# minimote.net
KiCad netlist of a schematic drawn in EAGLE
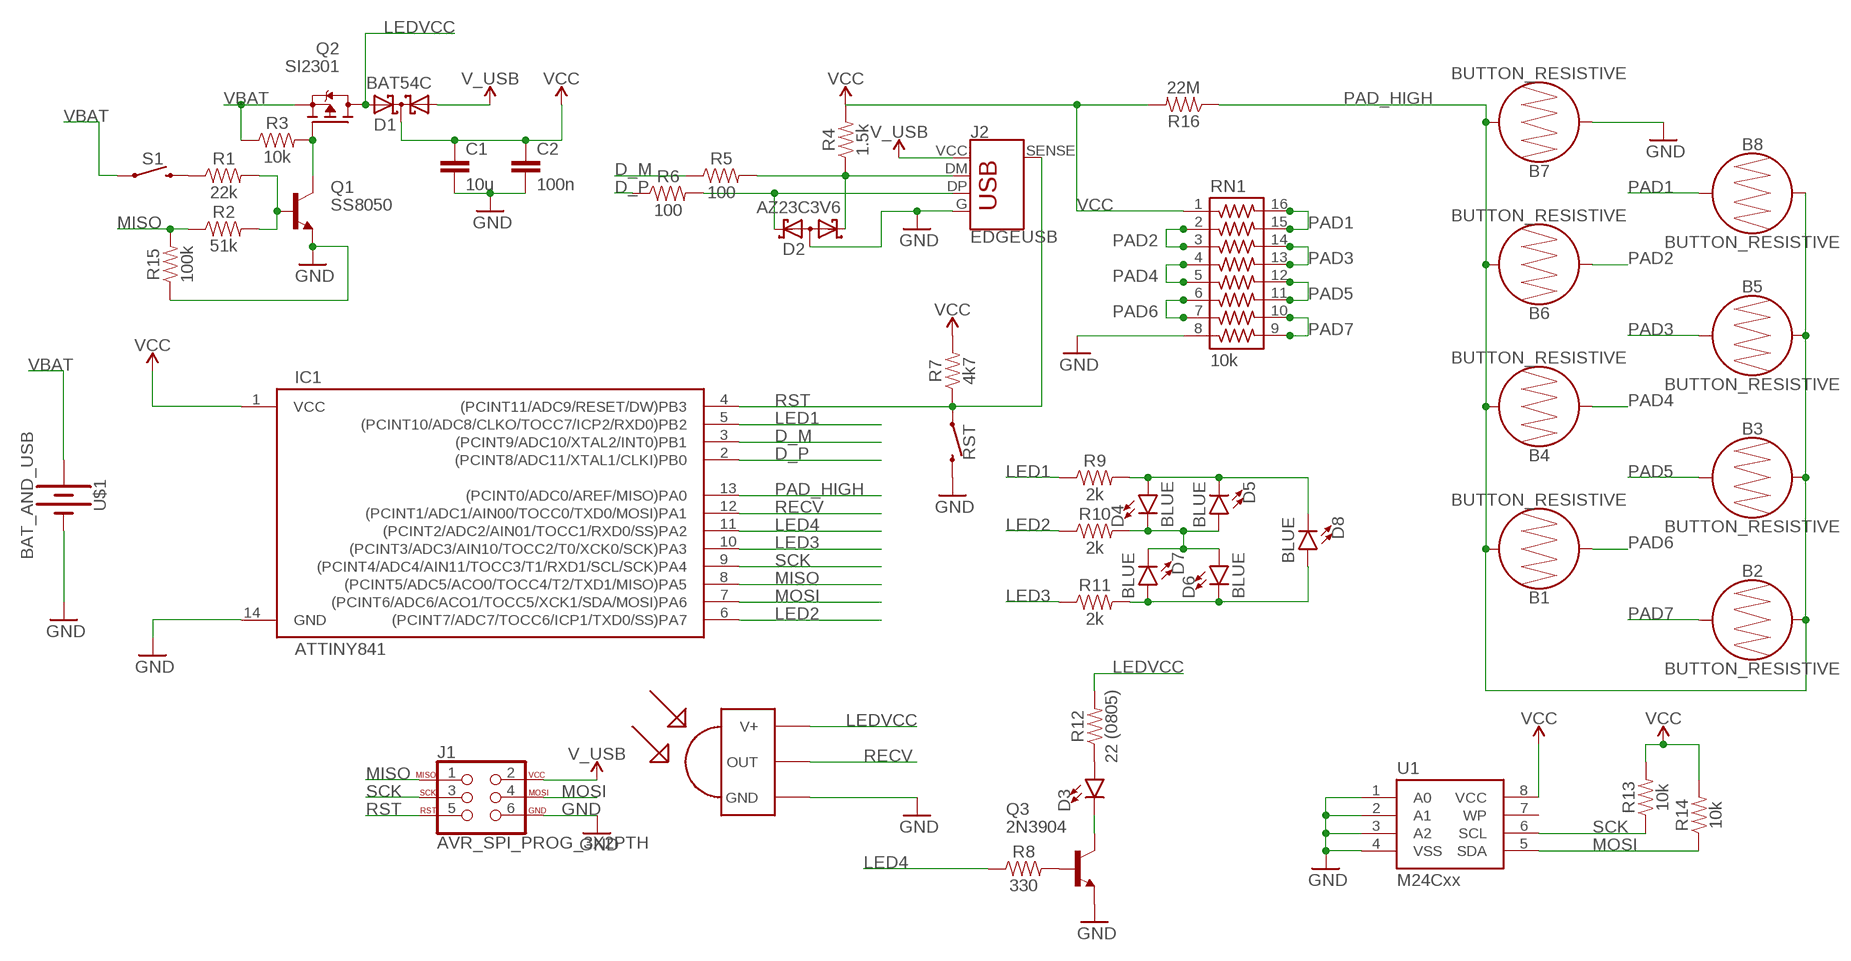
[diagram p0: schematic, sheet 1]

(export (version "E")
  (design (tool "Eeschema 10.0.6"))
  (components
    (comp (ref "B1")
      (value "BUTTON_RESISTIVE")
      (footprint "eagle-import:BUTTON-CONDUCTIVE")
      (libsource (lib "eagle-import") (part "BUTTON_RESISTIVE"))
    )
    (comp (ref "B2")
      (value "BUTTON_RESISTIVE")
      (footprint "eagle-import:BUTTON-CONDUCTIVE")
      (libsource (lib "eagle-import") (part "BUTTON_RESISTIVE"))
    )
    (comp (ref "B3")
      (value "BUTTON_RESISTIVE")
      (footprint "eagle-import:BUTTON-CONDUCTIVE")
      (libsource (lib "eagle-import") (part "BUTTON_RESISTIVE"))
    )
    (comp (ref "B4")
      (value "BUTTON_RESISTIVE")
      (footprint "eagle-import:BUTTON-CONDUCTIVE")
      (libsource (lib "eagle-import") (part "BUTTON_RESISTIVE"))
    )
    (comp (ref "B5")
      (value "BUTTON_RESISTIVE")
      (footprint "eagle-import:BUTTON-CONDUCTIVE")
      (libsource (lib "eagle-import") (part "BUTTON_RESISTIVE"))
    )
    (comp (ref "B6")
      (value "BUTTON_RESISTIVE")
      (footprint "eagle-import:BUTTON-CONDUCTIVE")
      (libsource (lib "eagle-import") (part "BUTTON_RESISTIVE"))
    )
    (comp (ref "B7")
      (value "BUTTON_RESISTIVE")
      (footprint "eagle-import:BUTTON-CONDUCTIVE")
      (libsource (lib "eagle-import") (part "BUTTON_RESISTIVE"))
    )
    (comp (ref "B8")
      (value "BUTTON_RESISTIVE")
      (footprint "eagle-import:BUTTON-CONDUCTIVE")
      (libsource (lib "eagle-import") (part "BUTTON_RESISTIVE"))
    )
    (comp (ref "C1")
      (value "10u")
      (footprint "eagle-import:0603")
      (libsource (lib "eagle-import") (part "10UF-0603-6.3V-20%"))
    )
    (comp (ref "C2")
      (value "100n")
      (footprint "eagle-import:0603")
      (libsource (lib "eagle-import") (part "10UF-0603-6.3V-20%"))
    )
    (comp (ref "D1")
      (value "BAT54C")
      (footprint "eagle-import:SOT23")
      (libsource (lib "eagle-import") (part "BAT54C"))
    )
    (comp (ref "D2")
      (value "AZ23C3V6")
      (footprint "eagle-import:SOT23")
      (libsource (lib "eagle-import") (part "AZ23C3V6"))
    )
    (comp (ref "D3")
      (value "LED3MM")
      (footprint "eagle-import:LED_3MM")
      (libsource (lib "eagle-import") (part "LED3MM"))
    )
    (comp (ref "D4")
      (value "BLUE")
      (footprint "eagle-import:LED-0603")
      (libsource (lib "eagle-import") (part "LED-BLUE0603"))
    )
    (comp (ref "D5")
      (value "BLUE")
      (footprint "eagle-import:LED-0603")
      (libsource (lib "eagle-import") (part "LED-BLUE0603"))
    )
    (comp (ref "D6")
      (value "BLUE")
      (footprint "eagle-import:LED-0603")
      (libsource (lib "eagle-import") (part "LED-BLUE0603"))
    )
    (comp (ref "D7")
      (value "BLUE")
      (footprint "eagle-import:LED-0603")
      (libsource (lib "eagle-import") (part "LED-BLUE0603"))
    )
    (comp (ref "D8")
      (value "BLUE")
      (footprint "eagle-import:LED-0603")
      (libsource (lib "eagle-import") (part "LED-BLUE0603"))
    )
    (comp (ref "IC1")
      (value "ATTINY841")
      (footprint "eagle-import:SOIC14N")
      (libsource (lib "eagle-import") (part "ATTINY441/841-SSU"))
    )
    (comp (ref "J1")
      (value "AVR_SPI_PROG_3X2PTH")
      (footprint "eagle-import:2X3")
      (libsource (lib "eagle-import") (part "AVR_SPI_PROG_3X2PTH"))
    )
    (comp (ref "J2")
      (value "EDGEUSB")
      (footprint "eagle-import:USBPCB")
      (libsource (lib "eagle-import") (part "EDGEUSB"))
    )
    (comp (ref "Q1")
      (value "SS8050")
      (footprint "eagle-import:SOT23")
      (libsource (lib "eagle-import") (part "SS8050"))
    )
    (comp (ref "Q2")
      (value "SI2301")
      (footprint "eagle-import:SOT23")
      (libsource (lib "eagle-import") (part "SI2301"))
    )
    (comp (ref "Q3")
      (value "2N3904")
      (footprint "eagle-import:SOT23-BEC")
      (libsource (lib "eagle-import") (part "-NPN-SOT23-BECMMBT3904LT1"))
    )
    (comp (ref "R1")
      (value "22k")
      (footprint "eagle-import:0603")
      (libsource (lib "eagle-import") (part "3.3KOHM-0603-1/10W-1%"))
    )
    (comp (ref "R2")
      (value "51k")
      (footprint "eagle-import:0603")
      (libsource (lib "eagle-import") (part "3.3KOHM-0603-1/10W-1%"))
    )
    (comp (ref "R3")
      (value "10k")
      (footprint "eagle-import:0603")
      (libsource (lib "eagle-import") (part "3.3KOHM-0603-1/10W-1%"))
    )
    (comp (ref "R4")
      (value "1.5k")
      (footprint "eagle-import:0603")
      (libsource (lib "eagle-import") (part "3.3KOHM-0603-1/10W-1%"))
    )
    (comp (ref "R5")
      (value "100")
      (footprint "eagle-import:0603")
      (libsource (lib "eagle-import") (part "3.3KOHM-0603-1/10W-1%"))
    )
    (comp (ref "R6")
      (value "100")
      (footprint "eagle-import:0603")
      (libsource (lib "eagle-import") (part "3.3KOHM-0603-1/10W-1%"))
    )
    (comp (ref "R7")
      (value "4k7")
      (footprint "eagle-import:0603")
      (libsource (lib "eagle-import") (part "3.3KOHM-0603-1/10W-1%"))
    )
    (comp (ref "R8")
      (value "330")
      (footprint "eagle-import:0603")
      (libsource (lib "eagle-import") (part "3.3KOHM-0603-1/10W-1%"))
    )
    (comp (ref "R9")
      (value "2k")
      (footprint "eagle-import:0603")
      (libsource (lib "eagle-import") (part "3.3KOHM-0603-1/10W-1%"))
    )
    (comp (ref "R10")
      (value "2k")
      (footprint "eagle-import:0603")
      (libsource (lib "eagle-import") (part "3.3KOHM-0603-1/10W-1%"))
    )
    (comp (ref "R11")
      (value "2k")
      (footprint "eagle-import:0603")
      (libsource (lib "eagle-import") (part "3.3KOHM-0603-1/10W-1%"))
    )
    (comp (ref "R12")
      (value "22 (0805)")
      (footprint "eagle-import:0805")
      (libsource (lib "eagle-import") (part "0.22OHM-0805-1/4W-1%"))
    )
    (comp (ref "R13")
      (value "10k")
      (footprint "eagle-import:0603")
      (libsource (lib "eagle-import") (part "3.3KOHM-0603-1/10W-1%"))
    )
    (comp (ref "R14")
      (value "10k")
      (footprint "eagle-import:0603")
      (libsource (lib "eagle-import") (part "3.3KOHM-0603-1/10W-1%"))
    )
    (comp (ref "R15")
      (value "100k")
      (footprint "eagle-import:0603")
      (libsource (lib "eagle-import") (part "3.3KOHM-0603-1/10W-1%"))
    )
    (comp (ref "R16")
      (value "22M")
      (footprint "eagle-import:0603")
      (libsource (lib "eagle-import") (part "3.3KOHM-0603-1/10W-1%"))
    )
    (comp (ref "RN1")
      (value "10k")
      (footprint "eagle-import:742-16NS")
      (libsource (lib "eagle-import") (part "742-16NS"))
    )
    (comp (ref "RST")
      (value "MOMENTARY-SWITCH-SPST-SMD-5.2-REDUNDANT")
      (footprint "eagle-import:TACTILE_SWITCH_SMD_5.2MM")
      (libsource (lib "eagle-import") (part "MOMENTARY-SWITCH-SPST-SMD-5.2-REDUNDANT"))
    )
    (comp (ref "S1")
      (value "MOMENTARY-SWITCH-SPST-SMD-5.2-REDUNDANT")
      (footprint "eagle-import:TACTILE_SWITCH_SMD_5.2MM")
      (libsource (lib "eagle-import") (part "MOMENTARY-SWITCH-SPST-SMD-5.2-REDUNDANT"))
    )
    (comp (ref "U$1")
      (value "BAT_AND_USB")
      (footprint "eagle-import:PUNCHOUT_USB")
      (libsource (lib "eagle-import") (part "BAT_AND_USB"))
    )
    (comp (ref "U$2")
      (value "TSOP1837")
      (footprint "eagle-import:TSOP18XX")
      (libsource (lib "eagle-import") (part "TSOP1837"))
    )
    (comp (ref "U1")
      (value "M24Cxx")
      (footprint "eagle-import:SO08-EIAJ")
      (libsource (lib "eagle-import") (part "EEPROM-I2CEIAJ"))
    )
  )
  (nets
    (net (code "1") (name "/D_M") (class "Default")
      (node (ref "IC1") (pin "3") (pinfunction "(PCINT9/ADC10/XTAL2/INT0)PB1_3") (pintype "bidirectional"))
      (node (ref "R5") (pin "1") (pinfunction "1_1") (pintype "passive"))
    )
    (net (code "2") (name "/D_P") (class "Default")
      (node (ref "IC1") (pin "2") (pinfunction "(PCINT8/ADC11/XTAL1/CLKI)PB0_2") (pintype "bidirectional"))
      (node (ref "R6") (pin "1") (pinfunction "1_1") (pintype "passive"))
    )
    (net (code "3") (name "/LED1") (class "Default")
      (node (ref "IC1") (pin "5") (pinfunction "(PCINT10/ADC8/CLKO/TOCC7/ICP2/RXD0)PB2_5") (pintype "bidirectional"))
      (node (ref "R9") (pin "1") (pinfunction "1_1") (pintype "passive"))
    )
    (net (code "4") (name "/LED2") (class "Default")
      (node (ref "IC1") (pin "6") (pinfunction "(PCINT7/ADC7/TOCC6/ICP1/TXD0/SS)PA7_6") (pintype "bidirectional"))
      (node (ref "R10") (pin "1") (pinfunction "1_1") (pintype "passive"))
    )
    (net (code "5") (name "/LED3") (class "Default")
      (node (ref "IC1") (pin "10") (pinfunction "(PCINT3/ADC3/AIN10/TOCC2/T0/XCK0/SCK)PA3_10") (pintype "bidirectional"))
      (node (ref "R11") (pin "1") (pinfunction "1_1") (pintype "passive"))
    )
    (net (code "6") (name "/LED4") (class "Default")
      (node (ref "IC1") (pin "11") (pinfunction "(PCINT2/ADC2/AIN01/TOCC1/RXD0/SS)PA2_11") (pintype "bidirectional"))
      (node (ref "R8") (pin "1") (pinfunction "1_1") (pintype "passive"))
    )
    (net (code "7") (name "/LEDVCC") (class "Default")
      (node (ref "D1") (pin "2") (pinfunction "A2_2") (pintype "passive"))
      (node (ref "Q2") (pin "3") (pinfunction "D_3") (pintype "passive"))
      (node (ref "R12") (pin "2") (pinfunction "2_2") (pintype "passive"))
      (node (ref "U$2") (pin "VCC") (pinfunction "V+_VCC") (pintype "bidirectional"))
    )
    (net (code "8") (name "/MISO") (class "Default")
      (node (ref "IC1") (pin "8") (pinfunction "(PCINT5/ADC5/ACO0/TOCC4/T2/TXD1/MISO)PA5_8") (pintype "bidirectional"))
      (node (ref "J1") (pin "1") (pinfunction "1_1") (pintype "passive"))
      (node (ref "R15") (pin "2") (pinfunction "2_2") (pintype "passive"))
      (node (ref "R2") (pin "1") (pinfunction "1_1") (pintype "passive"))
    )
    (net (code "9") (name "/MOSI") (class "Default")
      (node (ref "IC1") (pin "7") (pinfunction "(PCINT6/ADC6/ACO1/TOCC5/XCK1/SDA/MOSI)PA6_7") (pintype "bidirectional"))
      (node (ref "J1") (pin "4") (pinfunction "4_4") (pintype "passive"))
      (node (ref "R14") (pin "1") (pinfunction "1_1") (pintype "passive"))
      (node (ref "U1") (pin "5") (pinfunction "SDA_5") (pintype "bidirectional"))
    )
    (net (code "10") (name "/PAD1") (class "Default")
      (node (ref "B8") (pin "1") (pinfunction "1_1") (pintype "passive"))
      (node (ref "RN1") (pin "15") (pinfunction "15_15") (pintype "passive"))
      (node (ref "RN1") (pin "16") (pinfunction "16_16") (pintype "passive"))
    )
    (net (code "11") (name "/PAD2") (class "Default")
      (node (ref "B6") (pin "1") (pinfunction "1_1") (pintype "passive"))
      (node (ref "RN1") (pin "2") (pinfunction "2_2") (pintype "passive"))
      (node (ref "RN1") (pin "3") (pinfunction "3_3") (pintype "passive"))
    )
    (net (code "12") (name "/PAD3") (class "Default")
      (node (ref "B5") (pin "1") (pinfunction "1_1") (pintype "passive"))
      (node (ref "RN1") (pin "13") (pinfunction "13_13") (pintype "passive"))
      (node (ref "RN1") (pin "14") (pinfunction "14_14") (pintype "passive"))
    )
    (net (code "13") (name "/PAD4") (class "Default")
      (node (ref "B4") (pin "1") (pinfunction "1_1") (pintype "passive"))
      (node (ref "RN1") (pin "4") (pinfunction "4_4") (pintype "passive"))
      (node (ref "RN1") (pin "5") (pinfunction "5_5") (pintype "passive"))
    )
    (net (code "14") (name "/PAD5") (class "Default")
      (node (ref "B3") (pin "1") (pinfunction "1_1") (pintype "passive"))
      (node (ref "RN1") (pin "11") (pinfunction "11_11") (pintype "passive"))
      (node (ref "RN1") (pin "12") (pinfunction "12_12") (pintype "passive"))
    )
    (net (code "15") (name "/PAD6") (class "Default")
      (node (ref "B1") (pin "1") (pinfunction "1_1") (pintype "passive"))
      (node (ref "RN1") (pin "6") (pinfunction "6_6") (pintype "passive"))
      (node (ref "RN1") (pin "7") (pinfunction "7_7") (pintype "passive"))
    )
    (net (code "16") (name "/PAD7") (class "Default")
      (node (ref "B2") (pin "1") (pinfunction "1_1") (pintype "passive"))
      (node (ref "RN1") (pin "10") (pinfunction "10_10") (pintype "passive"))
      (node (ref "RN1") (pin "9") (pinfunction "9_9") (pintype "passive"))
    )
    (net (code "17") (name "/PAD_HIGH") (class "Default")
      (node (ref "B1") (pin "2") (pinfunction "2_2") (pintype "passive"))
      (node (ref "B2") (pin "2") (pinfunction "2_2") (pintype "passive"))
      (node (ref "B3") (pin "2") (pinfunction "2_2") (pintype "passive"))
      (node (ref "B4") (pin "2") (pinfunction "2_2") (pintype "passive"))
      (node (ref "B5") (pin "2") (pinfunction "2_2") (pintype "passive"))
      (node (ref "B6") (pin "2") (pinfunction "2_2") (pintype "passive"))
      (node (ref "B7") (pin "2") (pinfunction "2_2") (pintype "passive"))
      (node (ref "B8") (pin "2") (pinfunction "2_2") (pintype "passive"))
      (node (ref "IC1") (pin "13") (pinfunction "(PCINT0/ADC0/AREF/MISO)PA0_13") (pintype "bidirectional"))
      (node (ref "R16") (pin "1") (pinfunction "1_1") (pintype "passive"))
    )
    (net (code "18") (name "/RECV") (class "Default")
      (node (ref "IC1") (pin "12") (pinfunction "(PCINT1/ADC1/AIN00/TOCC0/TXD0/MOSI)PA1_12") (pintype "bidirectional"))
      (node (ref "U$2") (pin "OUT") (pinfunction "OUT_OUT") (pintype "bidirectional"))
    )
    (net (code "19") (name "/RST") (class "Default")
      (node (ref "IC1") (pin "4") (pinfunction "(PCINT11/ADC9/RESET/DW)PB3_4") (pintype "bidirectional"))
      (node (ref "J1") (pin "5") (pinfunction "5_5") (pintype "passive"))
      (node (ref "J2") (pin "SENSE") (pinfunction "SENSE_SENSE") (pintype "power_in"))
      (node (ref "R7") (pin "1") (pinfunction "1_1") (pintype "passive"))
      (node (ref "RST") (pin "1") (pinfunction "1_1") (pintype "passive"))
      (node (ref "RST") (pin "2") (pinfunction "1_2") (pintype "passive"))
    )
    (net (code "20") (name "/SCK") (class "Default")
      (node (ref "IC1") (pin "9") (pinfunction "(PCINT4/ADC4/AIN11/TOCC3/T1/RXD1/SCL/SCK)PA4_9") (pintype "bidirectional"))
      (node (ref "J1") (pin "3") (pinfunction "3_3") (pintype "passive"))
      (node (ref "R13") (pin "1") (pinfunction "1_1") (pintype "passive"))
      (node (ref "U1") (pin "6") (pinfunction "SCL_6") (pintype "bidirectional"))
    )
    (net (code "21") (name "/VBAT") (class "Default")
      (node (ref "Q2") (pin "2") (pinfunction "S_2") (pintype "passive"))
      (node (ref "R3") (pin "1") (pinfunction "1_1") (pintype "passive"))
      (node (ref "S1") (pin "1") (pinfunction "1_1") (pintype "passive"))
      (node (ref "S1") (pin "2") (pinfunction "1_2") (pintype "passive"))
      (node (ref "U$1") (pin "B+") (pinfunction "+_B+") (pintype "power_in"))
    )
    (net (code "22") (name "GND") (class "Default")
      (node (ref "B7") (pin "1") (pinfunction "1_1") (pintype "passive"))
      (node (ref "C1") (pin "2") (pinfunction "2_2") (pintype "passive"))
      (node (ref "C2") (pin "2") (pinfunction "2_2") (pintype "passive"))
      (node (ref "D2") (pin "3") (pinfunction "AA_3") (pintype "passive"))
      (node (ref "IC1") (pin "14") (pinfunction "GND_14") (pintype "bidirectional"))
      (node (ref "J1") (pin "6") (pinfunction "6_6") (pintype "passive"))
      (node (ref "J2") (pin "G") (pinfunction "GND_G") (pintype "power_in"))
      (node (ref "Q1") (pin "2") (pinfunction "E_2") (pintype "passive"))
      (node (ref "Q3") (pin "E") (pinfunction "E_E") (pintype "passive"))
      (node (ref "R15") (pin "1") (pinfunction "1_1") (pintype "passive"))
      (node (ref "RN1") (pin "8") (pinfunction "8_8") (pintype "passive"))
      (node (ref "RST") (pin "3") (pinfunction "2_3") (pintype "passive"))
      (node (ref "RST") (pin "4") (pinfunction "2_4") (pintype "passive"))
      (node (ref "U$1") (pin "B-") (pinfunction "-_B-") (pintype "power_in"))
      (node (ref "U$2") (pin "GND") (pinfunction "GND_GND") (pintype "bidirectional"))
      (node (ref "U1") (pin "1") (pinfunction "A0_1") (pintype "bidirectional"))
      (node (ref "U1") (pin "2") (pinfunction "A1_2") (pintype "bidirectional"))
      (node (ref "U1") (pin "3") (pinfunction "A2_3") (pintype "bidirectional"))
      (node (ref "U1") (pin "4") (pinfunction "VSS_4") (pintype "power_in"))
    )
    (net (code "23") (name "Net-(D2-K1)") (class "Default")
      (node (ref "D2") (pin "2") (pinfunction "K1_2") (pintype "passive"))
      (node (ref "J2") (pin "DM") (pinfunction "D-_DM") (pintype "bidirectional"))
      (node (ref "R4") (pin "1") (pinfunction "1_1") (pintype "passive"))
      (node (ref "R5") (pin "2") (pinfunction "2_2") (pintype "passive"))
    )
    (net (code "24") (name "Net-(D2-K2)") (class "Default")
      (node (ref "D2") (pin "1") (pinfunction "K2_1") (pintype "passive"))
      (node (ref "J2") (pin "DP") (pinfunction "D+_DP") (pintype "bidirectional"))
      (node (ref "R6") (pin "2") (pinfunction "2_2") (pintype "passive"))
    )
    (net (code "25") (name "Net-(D3-C)") (class "Default")
      (node (ref "D3") (pin "K") (pinfunction "C_K") (pintype "passive"))
      (node (ref "Q3") (pin "C") (pinfunction "C_C") (pintype "passive"))
    )
    (net (code "26") (name "Net-(D3-PadA)") (class "Default")
      (node (ref "D3") (pin "A") (pinfunction "A_A") (pintype "passive"))
      (node (ref "R12") (pin "1") (pinfunction "1_1") (pintype "passive"))
    )
    (net (code "27") (name "Net-(D4-PadA)") (class "Default")
      (node (ref "D4") (pin "A") (pinfunction "A_A") (pintype "passive"))
      (node (ref "D5") (pin "C") (pinfunction "C_C") (pintype "passive"))
      (node (ref "D8") (pin "C") (pinfunction "C_C") (pintype "passive"))
      (node (ref "R9") (pin "2") (pinfunction "2_2") (pintype "passive"))
    )
    (net (code "28") (name "Net-(D4-PadC)") (class "Default")
      (node (ref "D4") (pin "C") (pinfunction "C_C") (pintype "passive"))
      (node (ref "D5") (pin "A") (pinfunction "A_A") (pintype "passive"))
      (node (ref "D6") (pin "A") (pinfunction "A_A") (pintype "passive"))
      (node (ref "D7") (pin "C") (pinfunction "C_C") (pintype "passive"))
      (node (ref "R10") (pin "2") (pinfunction "2_2") (pintype "passive"))
    )
    (net (code "29") (name "Net-(D6-PadC)") (class "Default")
      (node (ref "D6") (pin "C") (pinfunction "C_C") (pintype "passive"))
      (node (ref "D7") (pin "A") (pinfunction "A_A") (pintype "passive"))
      (node (ref "D8") (pin "A") (pinfunction "A_A") (pintype "passive"))
      (node (ref "R11") (pin "2") (pinfunction "2_2") (pintype "passive"))
    )
    (net (code "30") (name "Net-(Q1-B)") (class "Default")
      (node (ref "Q1") (pin "1") (pinfunction "B_1") (pintype "passive"))
      (node (ref "R1") (pin "2") (pinfunction "2_2") (pintype "passive"))
      (node (ref "R2") (pin "2") (pinfunction "2_2") (pintype "passive"))
    )
    (net (code "31") (name "Net-(Q1-C)") (class "Default")
      (node (ref "Q1") (pin "3") (pinfunction "C_3") (pintype "passive"))
      (node (ref "Q2") (pin "1") (pinfunction "G_1") (pintype "passive"))
      (node (ref "R3") (pin "2") (pinfunction "2_2") (pintype "passive"))
    )
    (net (code "32") (name "Net-(Q3-PadB)") (class "Default")
      (node (ref "Q3") (pin "B") (pinfunction "B_B") (pintype "passive"))
      (node (ref "R8") (pin "2") (pinfunction "2_2") (pintype "passive"))
    )
    (net (code "33") (name "Net-(R1-Pad1)") (class "Default")
      (node (ref "R1") (pin "1") (pinfunction "1_1") (pintype "passive"))
      (node (ref "S1") (pin "3") (pinfunction "2_3") (pintype "passive"))
      (node (ref "S1") (pin "4") (pinfunction "2_4") (pintype "passive"))
    )
    (net (code "34") (name "VCC") (class "Default")
      (node (ref "C1") (pin "1") (pinfunction "1_1") (pintype "passive"))
      (node (ref "C2") (pin "1") (pinfunction "1_1") (pintype "passive"))
      (node (ref "D1") (pin "3") (pinfunction "CC_3") (pintype "passive"))
      (node (ref "IC1") (pin "1") (pinfunction "VCC_1") (pintype "bidirectional"))
      (node (ref "R13") (pin "2") (pinfunction "2_2") (pintype "passive"))
      (node (ref "R14") (pin "2") (pinfunction "2_2") (pintype "passive"))
      (node (ref "R16") (pin "2") (pinfunction "2_2") (pintype "passive"))
      (node (ref "R4") (pin "2") (pinfunction "2_2") (pintype "passive"))
      (node (ref "R7") (pin "2") (pinfunction "2_2") (pintype "passive"))
      (node (ref "RN1") (pin "1") (pinfunction "1_1") (pintype "passive"))
      (node (ref "U1") (pin "8") (pinfunction "VCC_8") (pintype "power_in"))
    )
    (net (code "35") (name "V_USB") (class "Default")
      (node (ref "D1") (pin "1") (pinfunction "A1_1") (pintype "passive"))
      (node (ref "J1") (pin "2") (pinfunction "2_2") (pintype "passive"))
      (node (ref "J2") (pin "VCC") (pinfunction "VBUS_VCC") (pintype "power_in"))
    )
    (net (code "36") (name "unconnected-(U1-WP-Pad7)") (class "Default")
      (node (ref "U1") (pin "7") (pinfunction "WP_7") (pintype "bidirectional"))
    )
  )
)
